# SCH_Record-wav.net
KiCad netlist of a schematic drawn in EasyEDA
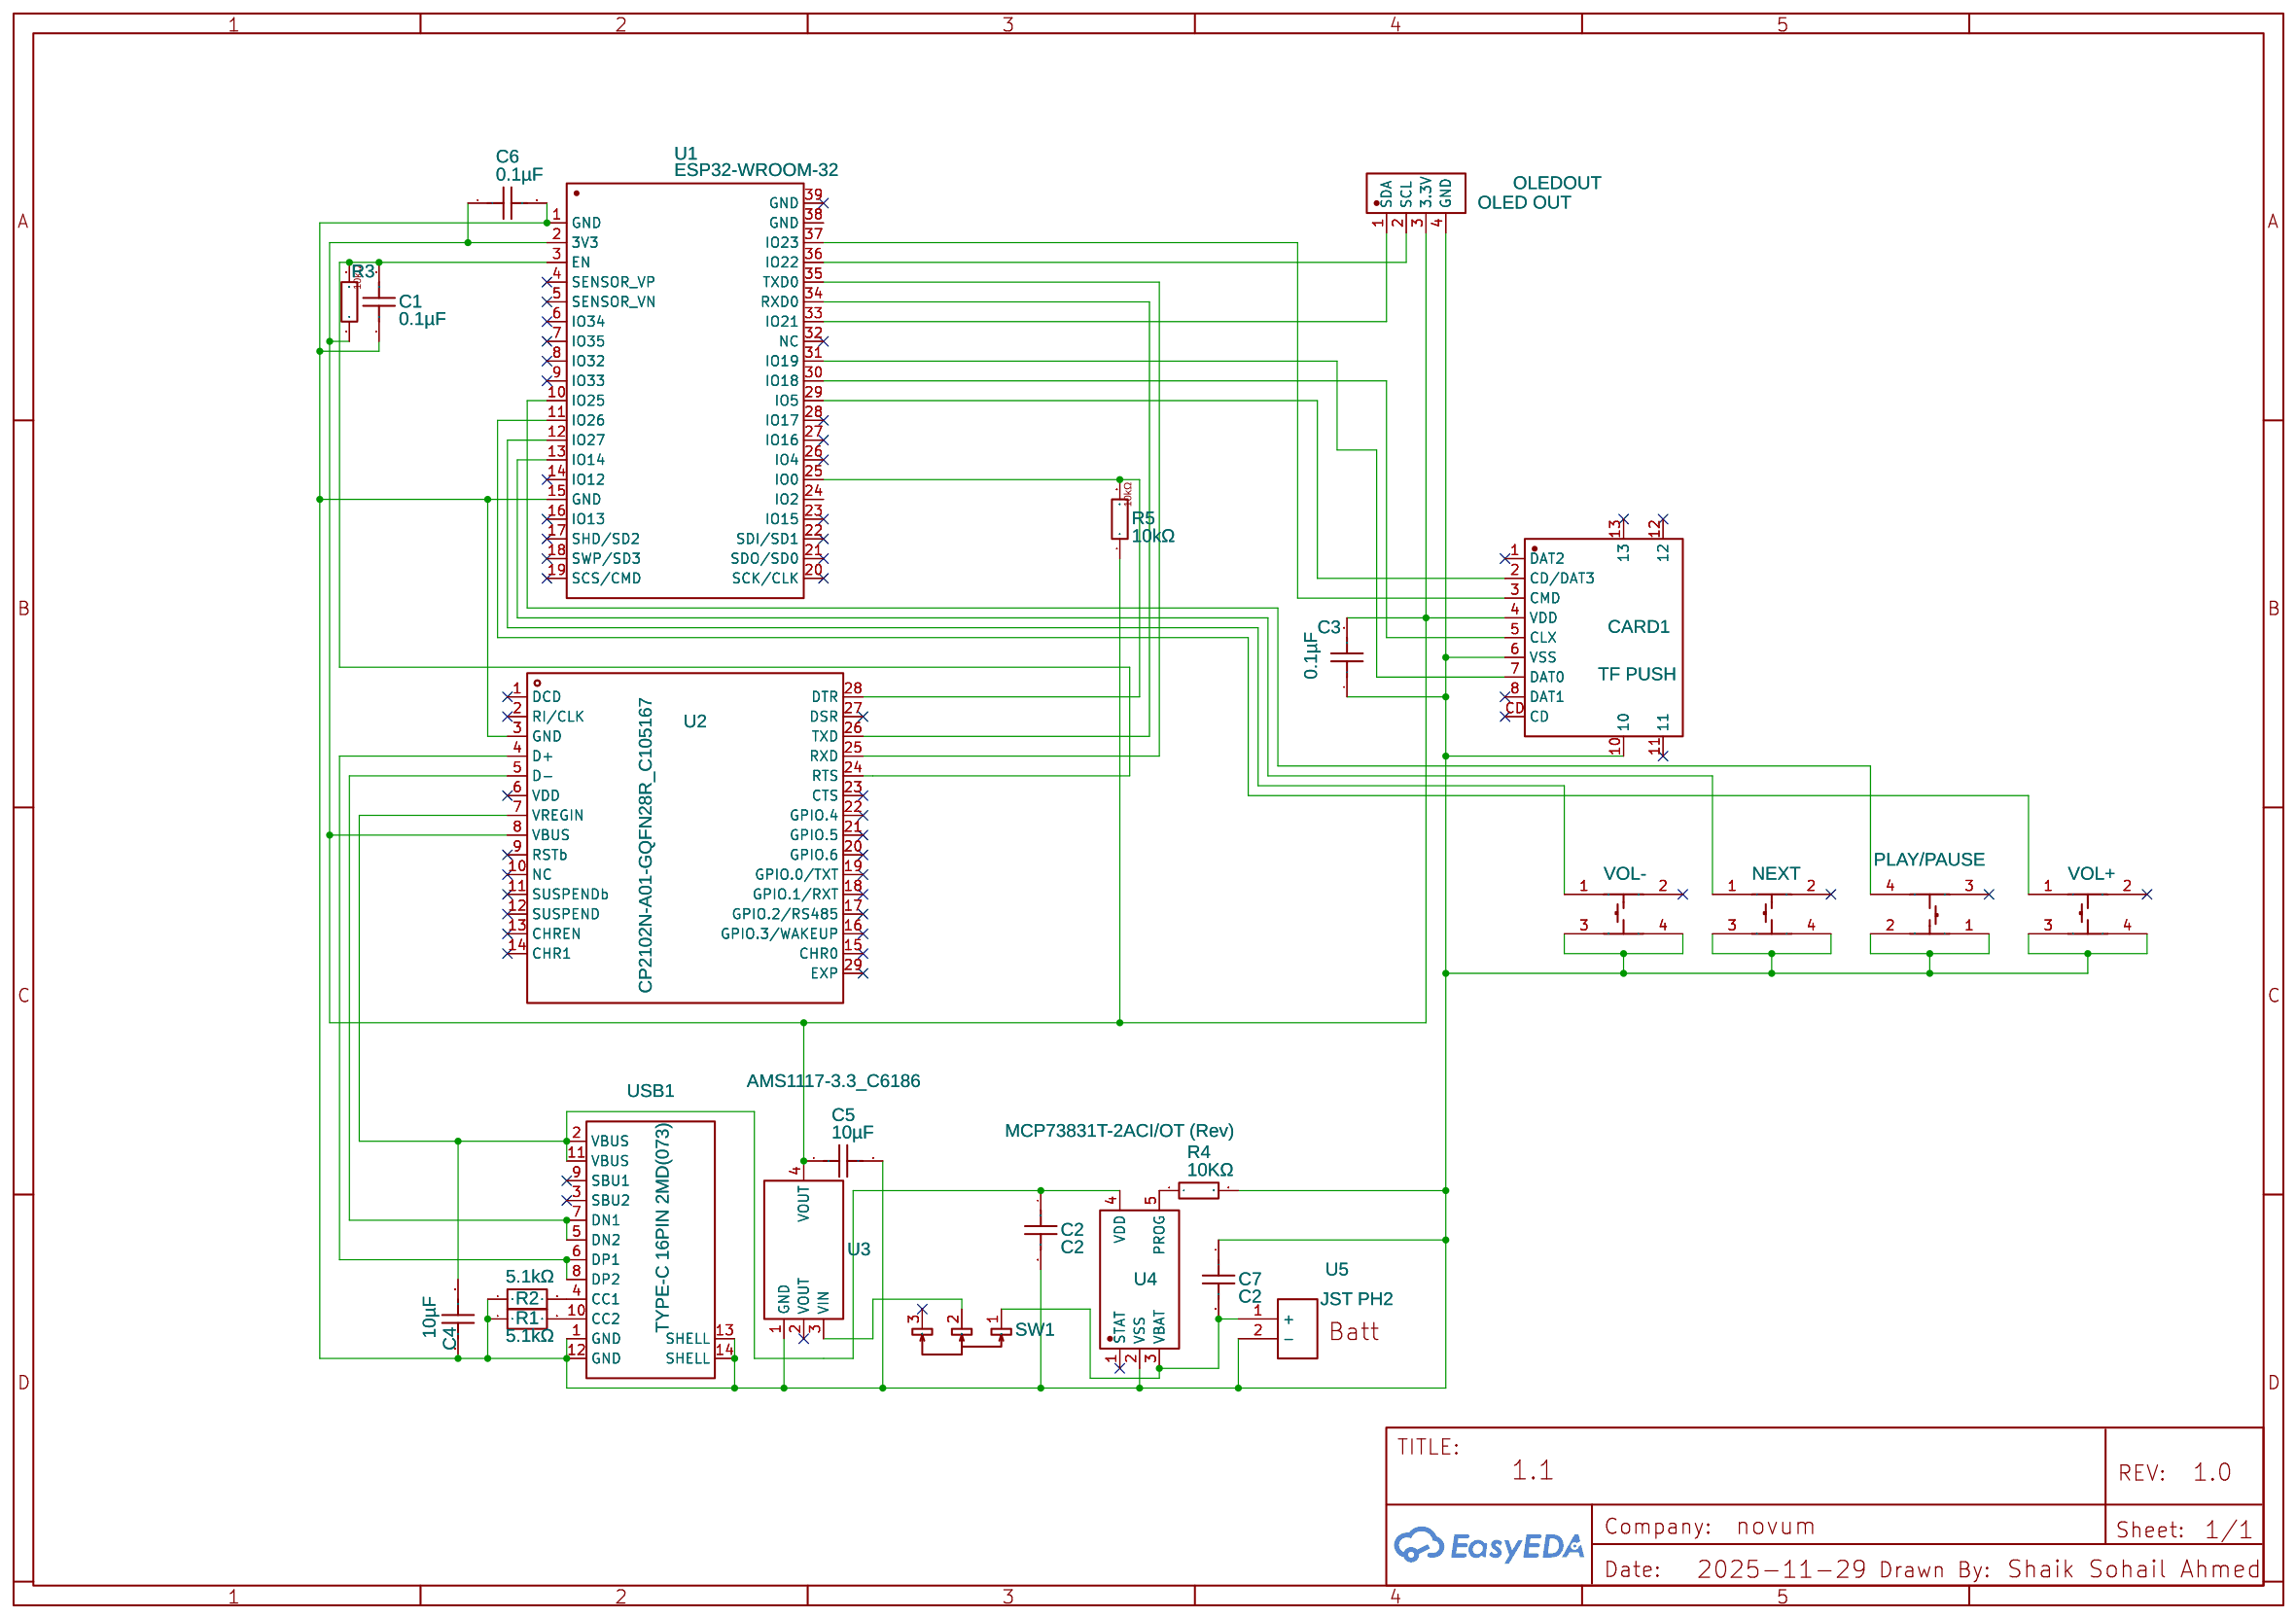
[diagram p0: schematic sheet]

(export (version "E")
  (design (tool "Eeschema 10.0.6"))
  (components
    (comp (ref "C1")
      (value "0.1µF")
      (fields (field (name "Manufacturer Part") "GRM152R60J104ME19D") (field (name "Manufacturer") "muRata"))
      (libsource (lib "") (part "0.1µF_1"))
    )
    (comp (ref "C2")
      (value "C2")
      (fields (field (name "Manufacturer Part") "08053C105JAT2A") (field (name "Manufacturer") "KYOCERA AVX"))
      (libsource (lib "") (part "08053C105JAT2A"))
    )
    (comp (ref "C3")
      (value "0.1µF")
      (fields (field (name "Manufacturer Part") "GRM152R60J104ME19D") (field (name "Manufacturer") "muRata"))
      (libsource (lib "") (part "0.1µF_1"))
    )
    (comp (ref "C4")
      (value "10µF")
      (fields
        (field (name "Manufacturer Part") "CL10A106MA8NRNC")
        (field (name "Manufacturer") "Samsung Electro-Mechanics")
      )
      (libsource (lib "") (part "CL10A106MA8NRNC"))
    )
    (comp (ref "C5")
      (value "10µF")
      (fields
        (field (name "Manufacturer Part") "CL10A106MA8NRNC")
        (field (name "Manufacturer") "Samsung Electro-Mechanics")
      )
      (libsource (lib "") (part "CL10A106MA8NRNC_1"))
    )
    (comp (ref "C6")
      (value "0.1µF")
      (fields (field (name "Manufacturer Part") "GRM152R60J104ME19D") (field (name "Manufacturer") "muRata"))
      (libsource (lib "") (part "0.1µF"))
    )
    (comp (ref "C7")
      (value "C2")
      (fields (field (name "Manufacturer Part") "08053C105JAT2A") (field (name "Manufacturer") "KYOCERA AVX"))
      (libsource (lib "") (part "08053C105JAT2A"))
    )
    (comp (ref "CARD1")
      (value "TF PUSH")
      (fields (field (name "Manufacturer") "SHOU HAN(首韩)"))
      (libsource (lib "") (part "TF PUSH"))
    )
    (comp (ref "NEXT")
      (value "TS-1002S-07026C")
      (fields (field (name "Manufacturer") "XUNPU(讯普)"))
      (libsource (lib "") (part "TS-1002S-07026C_2"))
    )
    (comp (ref "OLEDOUT") (value "OLED OUT") (libsource (lib "") (part "Solder_Pad_4")))
    (comp (ref "PLAY/PAUSE")
      (value "TS-1002S-07026C")
      (fields (field (name "Manufacturer") "XUNPU(讯普)"))
      (libsource (lib "") (part "TS-1002S-07026C_3"))
    )
    (comp (ref "R1")
      (value "5.1kΩ")
      (fields (field (name "Manufacturer Part") "FRC1206F5101TS") (field (name "Manufacturer") "FOJAN(富捷)"))
      (libsource (lib "") (part "5.1KΩ 1/4W ±1% SMD"))
    )
    (comp (ref "R2")
      (value "5.1kΩ")
      (fields (field (name "Manufacturer Part") "FRC1206F5101TS") (field (name "Manufacturer") "FOJAN(富捷)"))
      (libsource (lib "") (part "5.1KΩ 1/4W ±1% SMD"))
    )
    (comp (ref "R3") (value "10kΩ") (libsource (lib "") (part "10kΩ")))
    (comp (ref "R4")
      (value "10KΩ")
      (fields (field (name "Manufacturer Part") "CFR0W4J0103A50") (field (name "Manufacturer") "UniOhm"))
      (libsource (lib "") (part "10KΩ"))
    )
    (comp (ref "R5") (value "10kΩ") (libsource (lib "") (part "10kΩ")))
    (comp (ref "SW1")
      (value "MST-12D18G4 SPDT SLIDE SWITCH")
      (fields
        (field (name "Manufacturer Part") "MST-12D18G4 SPDT Slide Switch")
        (field (name "Manufacturer") "SHOU HAN(首韩)")
      )
      (libsource (lib "") (part "MST-12D18G4 SPDT SLIDE SWITCH"))
    )
    (comp (ref "U1")
      (value "ESP32-WROOM-32")
      (fields
        (field (name "Manufacturer Part") "ESP32-WROOM-32-N4")
        (field (name "Manufacturer") "ESPRESSIF(乐鑫)")
      )
      (libsource (lib "") (part "ESP32-WROOM-32"))
    )
    (comp (ref "U2")
      (value "CP2102N-A01-GQFN28R_C105167")
      (fields
        (field (name "Manufacturer Part") "CP2102N-A01-GQFN28R")
        (field (name "Manufacturer") "SKYWORKS/SILICON LABS(芯科)")
      )
      (libsource (lib "") (part "CP2102N-A01-GQFN28R_C105167"))
    )
    (comp (ref "U3")
      (value "AMS1117-3.3_C6186")
      (fields (field (name "Manufacturer Part") "AMS1117-3.3") (field (name "Manufacturer") "AMS"))
      (libsource (lib "") (part "AMS1117-3.3_C6186"))
    )
    (comp (ref "U4")
      (value "MCP73831T-2ACI/OT (Rev)")
      (fields
        (field (name "Manufacturer Part") "MCP73831T-2ACI/OT")
        (field (name "Manufacturer") "MICROCHIP(美国微芯)")
      )
      (libsource (lib "") (part "MCP73831T-2ACI/OT (Rev)"))
    )
    (comp (ref "U5") (value "JST PH2") (libsource (lib "") (part "JST PH2")))
    (comp (ref "USB1")
      (value "TYPE-C 16PIN 2MD(073)")
      (fields (field (name "Manufacturer") "SHOU HAN(首韩)"))
      (libsource (lib "") (part "TYPE-C 16PIN 2MD(073)"))
    )
    (comp (ref "VOL+")
      (value "TS-1002S-07026C")
      (fields (field (name "Manufacturer") "XUNPU(讯普)"))
      (libsource (lib "") (part "TS-1002S-07026C_1"))
    )
    (comp (ref "VOL-")
      (value "TS-1002S-07026C")
      (fields (field (name "Manufacturer") "XUNPU(讯普)"))
      (libsource (lib "") (part "TS-1002S-07026C"))
    )
  )
  (nets
    (net (code "1") (name "Net-(CARD1-CD{slash}DAT3)") (class "Default")
      (node (ref "CARD1") (pin "2") (pinfunction "CD/DAT3_2") (pintype "unspecified"))
      (node (ref "U1") (pin "29") (pinfunction "IO5_29") (pintype "unspecified"))
    )
    (net (code "2") (name "Net-(CARD1-CLX)") (class "Default")
      (node (ref "CARD1") (pin "5") (pinfunction "CLX_5") (pintype "unspecified"))
      (node (ref "U1") (pin "30") (pinfunction "IO18_30") (pintype "unspecified"))
    )
    (net (code "3") (name "Net-(CARD1-CMD)") (class "Default")
      (node (ref "CARD1") (pin "3") (pinfunction "CMD_3") (pintype "unspecified"))
      (node (ref "U1") (pin "37") (pinfunction "IO23_37") (pintype "unspecified"))
    )
    (net (code "4") (name "Net-(CARD1-DAT0)") (class "Default")
      (node (ref "CARD1") (pin "7") (pinfunction "DAT0_7") (pintype "unspecified"))
      (node (ref "U1") (pin "31") (pinfunction "IO19_31") (pintype "unspecified"))
    )
    (net (code "5") (name "Net-(CARD1-VDD)") (class "Default")
      (node (ref "C3") (pin "2") (pinfunction "2_2") (pintype "unspecified"))
      (node (ref "C5") (pin "1") (pinfunction "1_1") (pintype "unspecified"))
      (node (ref "C6") (pin "1") (pinfunction "1_1") (pintype "unspecified"))
      (node (ref "CARD1") (pin "4") (pinfunction "VDD_4") (pintype "unspecified"))
      (node (ref "OLEDOUT") (pin "3") (pinfunction "3.3V_3") (pintype "unspecified"))
      (node (ref "R3") (pin "1") (pinfunction "1_1") (pintype "unspecified"))
      (node (ref "R5") (pin "1") (pinfunction "1_1") (pintype "unspecified"))
      (node (ref "U1") (pin "2") (pinfunction "3V3_2") (pintype "unspecified"))
      (node (ref "U2") (pin "8") (pinfunction "VBUS_8") (pintype "unspecified"))
      (node (ref "U3") (pin "4") (pinfunction "VOUT_4") (pintype "unspecified"))
    )
    (net (code "6") (name "Net-(CARD1-VSS)") (class "Default")
      (node (ref "C1") (pin "1") (pinfunction "1_1") (pintype "unspecified"))
      (node (ref "C2") (pin "2") (pinfunction "2_2") (pintype "unspecified"))
      (node (ref "C3") (pin "1") (pinfunction "1_1") (pintype "unspecified"))
      (node (ref "C4") (pin "2") (pinfunction "2_2") (pintype "unspecified"))
      (node (ref "C5") (pin "2") (pinfunction "2_2") (pintype "unspecified"))
      (node (ref "C6") (pin "2") (pinfunction "2_2") (pintype "unspecified"))
      (node (ref "C7") (pin "1") (pinfunction "1_1") (pintype "unspecified"))
      (node (ref "CARD1") (pin "10") (pinfunction "10_10") (pintype "unspecified"))
      (node (ref "CARD1") (pin "6") (pinfunction "VSS_6") (pintype "unspecified"))
      (node (ref "NEXT") (pin "3") (pinfunction "3_3") (pintype "unspecified"))
      (node (ref "NEXT") (pin "4") (pinfunction "4_4") (pintype "unspecified"))
      (node (ref "OLEDOUT") (pin "4") (pinfunction "GND_4") (pintype "unspecified"))
      (node (ref "PLAY/PAUSE") (pin "1") (pinfunction "1_1") (pintype "unspecified"))
      (node (ref "PLAY/PAUSE") (pin "2") (pinfunction "2_2") (pintype "unspecified"))
      (node (ref "R1") (pin "1") (pinfunction "1_1") (pintype "unspecified"))
      (node (ref "R2") (pin "1") (pinfunction "1_1") (pintype "unspecified"))
      (node (ref "R4") (pin "2") (pinfunction "2_2") (pintype "input"))
      (node (ref "U1") (pin "1") (pinfunction "GND_1") (pintype "unspecified"))
      (node (ref "U1") (pin "15") (pinfunction "GND_15") (pintype "unspecified"))
      (node (ref "U2") (pin "3") (pinfunction "GND_3") (pintype "unspecified"))
      (node (ref "U3") (pin "1") (pinfunction "GND_1") (pintype "unspecified"))
      (node (ref "U4") (pin "2") (pinfunction "VSS_2") (pintype "unspecified"))
      (node (ref "U5") (pin "2") (pinfunction "-_2") (pintype "unspecified"))
      (node (ref "USB1") (pin "1") (pinfunction "GND_1") (pintype "unspecified"))
      (node (ref "USB1") (pin "12") (pinfunction "GND_12") (pintype "unspecified"))
      (node (ref "USB1") (pin "13") (pinfunction "SHELL_13") (pintype "unspecified"))
      (node (ref "USB1") (pin "14") (pinfunction "SHELL_14") (pintype "unspecified"))
      (node (ref "VOL+") (pin "3") (pinfunction "3_3") (pintype "unspecified"))
      (node (ref "VOL+") (pin "4") (pinfunction "4_4") (pintype "unspecified"))
      (node (ref "VOL-") (pin "3") (pinfunction "3_3") (pintype "unspecified"))
      (node (ref "VOL-") (pin "4") (pinfunction "4_4") (pintype "unspecified"))
    )
    (net (code "7") (name "Net-(OLEDOUT-SCL)") (class "Default")
      (node (ref "OLEDOUT") (pin "2") (pinfunction "SCL_2") (pintype "unspecified"))
      (node (ref "U1") (pin "36") (pinfunction "IO22_36") (pintype "unspecified"))
    )
    (net (code "8") (name "Net-(OLEDOUT-SDA)") (class "Default")
      (node (ref "OLEDOUT") (pin "1") (pinfunction "SDA_1") (pintype "unspecified"))
      (node (ref "U1") (pin "33") (pinfunction "IO21_33") (pintype "unspecified"))
    )
    (net (code "9") (name "Net-(U1-EN)") (class "Default")
      (node (ref "C1") (pin "2") (pinfunction "2_2") (pintype "unspecified"))
      (node (ref "R3") (pin "2") (pinfunction "2_2") (pintype "unspecified"))
      (node (ref "U1") (pin "3") (pinfunction "EN_3") (pintype "unspecified"))
      (node (ref "U2") (pin "24") (pinfunction "RTS_24") (pintype "unspecified"))
    )
    (net (code "10") (name "Net-(U1-IO0)") (class "Default")
      (node (ref "R5") (pin "2") (pinfunction "2_2") (pintype "unspecified"))
      (node (ref "U1") (pin "25") (pinfunction "IO0_25") (pintype "unspecified"))
      (node (ref "U2") (pin "28") (pinfunction "DTR_28") (pintype "unspecified"))
    )
    (net (code "11") (name "Net-(U1-IO14)") (class "Default")
      (node (ref "NEXT") (pin "1") (pinfunction "1_1") (pintype "unspecified"))
      (node (ref "U1") (pin "13") (pinfunction "IO14_13") (pintype "unspecified"))
    )
    (net (code "12") (name "Net-(U1-IO25)") (class "Default")
      (node (ref "PLAY/PAUSE") (pin "4") (pinfunction "4_4") (pintype "unspecified"))
      (node (ref "U1") (pin "10") (pinfunction "IO25_10") (pintype "unspecified"))
    )
    (net (code "13") (name "Net-(U1-IO26)") (class "Default")
      (node (ref "U1") (pin "11") (pinfunction "IO26_11") (pintype "unspecified"))
      (node (ref "VOL+") (pin "1") (pinfunction "1_1") (pintype "unspecified"))
    )
    (net (code "14") (name "Net-(U1-IO27)") (class "Default")
      (node (ref "U1") (pin "12") (pinfunction "IO27_12") (pintype "unspecified"))
      (node (ref "VOL-") (pin "1") (pinfunction "1_1") (pintype "unspecified"))
    )
    (net (code "15") (name "Net-(U1-RXD0)") (class "Default")
      (node (ref "U1") (pin "34") (pinfunction "RXD0_34") (pintype "unspecified"))
      (node (ref "U2") (pin "26") (pinfunction "TXD_26") (pintype "unspecified"))
    )
    (net (code "16") (name "Net-(U1-TXD0)") (class "Default")
      (node (ref "U1") (pin "35") (pinfunction "TXD0_35") (pintype "unspecified"))
      (node (ref "U2") (pin "25") (pinfunction "RXD_25") (pintype "unspecified"))
    )
    (net (code "17") (name "Net-(U2-D+)") (class "Default")
      (node (ref "U2") (pin "4") (pinfunction "D+_4") (pintype "unspecified"))
      (node (ref "USB1") (pin "6") (pinfunction "DP1_6") (pintype "unspecified"))
      (node (ref "USB1") (pin "8") (pinfunction "DP2_8") (pintype "unspecified"))
    )
    (net (code "18") (name "Net-(U2-D-)") (class "Default")
      (node (ref "U2") (pin "5") (pinfunction "D-_5") (pintype "unspecified"))
      (node (ref "USB1") (pin "5") (pinfunction "DN2_5") (pintype "unspecified"))
      (node (ref "USB1") (pin "7") (pinfunction "DN1_7") (pintype "unspecified"))
    )
    (net (code "19") (name "Net-(U2-VREGIN)") (class "Default")
      (node (ref "C2") (pin "1") (pinfunction "1_1") (pintype "unspecified"))
      (node (ref "C4") (pin "1") (pinfunction "1_1") (pintype "unspecified"))
      (node (ref "U2") (pin "7") (pinfunction "VREGIN_7") (pintype "unspecified"))
      (node (ref "U4") (pin "4") (pinfunction "VDD_4") (pintype "unspecified"))
      (node (ref "USB1") (pin "11") (pinfunction "VBUS_11") (pintype "unspecified"))
      (node (ref "USB1") (pin "2") (pinfunction "VBUS_2") (pintype "unspecified"))
    )
    (net (code "20") (name "Net-(U3-VIN)") (class "Default")
      (node (ref "SW1") (pin "2") (pinfunction "2_2") (pintype "unspecified"))
      (node (ref "U3") (pin "3") (pinfunction "VIN_3") (pintype "unspecified"))
    )
    (net (code "21") (name "Net-(U4-PROG)") (class "Default")
      (node (ref "R4") (pin "1") (pinfunction "1_1") (pintype "input"))
      (node (ref "U4") (pin "5") (pinfunction "PROG_5") (pintype "unspecified"))
    )
    (net (code "22") (name "Net-(U4-VBAT)") (class "Default")
      (node (ref "C7") (pin "2") (pinfunction "2_2") (pintype "unspecified"))
      (node (ref "SW1") (pin "1") (pinfunction "1_1") (pintype "unspecified"))
      (node (ref "U4") (pin "3") (pinfunction "VBAT_3") (pintype "unspecified"))
      (node (ref "U5") (pin "1") (pinfunction "+_1") (pintype "unspecified"))
    )
    (net (code "23") (name "Net-(USB1-CC1)") (class "Default")
      (node (ref "R2") (pin "2") (pinfunction "2_2") (pintype "unspecified"))
      (node (ref "USB1") (pin "4") (pinfunction "CC1_4") (pintype "unspecified"))
    )
    (net (code "24") (name "Net-(USB1-CC2)") (class "Default")
      (node (ref "R1") (pin "2") (pinfunction "2_2") (pintype "unspecified"))
      (node (ref "USB1") (pin "10") (pinfunction "CC2_10") (pintype "unspecified"))
    )
    (net (code "25") (name "unconnected-(CARD1-DAT1-Pad8)") (class "Default")
      (node (ref "CARD1") (pin "8") (pinfunction "DAT1_8") (pintype "unspecified+no_connect"))
    )
    (net (code "26") (name "unconnected-(CARD1-DAT2-Pad1)") (class "Default")
      (node (ref "CARD1") (pin "1") (pinfunction "DAT2_1") (pintype "unspecified+no_connect"))
    )
    (net (code "27") (name "unconnected-(CARD1-Pad11)") (class "Default")
      (node (ref "CARD1") (pin "11") (pinfunction "11_11") (pintype "unspecified+no_connect"))
    )
    (net (code "28") (name "unconnected-(CARD1-Pad12)") (class "Default")
      (node (ref "CARD1") (pin "12") (pinfunction "12_12") (pintype "unspecified+no_connect"))
    )
    (net (code "29") (name "unconnected-(CARD1-Pad13)") (class "Default")
      (node (ref "CARD1") (pin "13") (pinfunction "13_13") (pintype "unspecified+no_connect"))
    )
    (net (code "30") (name "unconnected-(CARD1-PadCD)") (class "Default")
      (node (ref "CARD1") (pin "CD") (pinfunction "CD_CD") (pintype "unspecified+no_connect"))
    )
    (net (code "31") (name "unconnected-(NEXT-Pad2)") (class "Default")
      (node (ref "NEXT") (pin "2") (pinfunction "2_2") (pintype "unspecified+no_connect"))
    )
    (net (code "32") (name "unconnected-(PLAY/PAUSE-Pad3)") (class "Default")
      (node (ref "PLAY/PAUSE") (pin "3") (pinfunction "3_3") (pintype "unspecified+no_connect"))
    )
    (net (code "33") (name "unconnected-(SW1-Pad3)") (class "Default")
      (node (ref "SW1") (pin "3") (pinfunction "3_3") (pintype "unspecified+no_connect"))
    )
    (net (code "34") (name "unconnected-(U1-GND-Pad38)") (class "Default")
      (node (ref "U1") (pin "38") (pinfunction "GND_38") (pintype "unspecified"))
    )
    (net (code "35") (name "unconnected-(U1-GND-Pad39)") (class "Default")
      (node (ref "U1") (pin "39") (pinfunction "GND_39") (pintype "unspecified+no_connect"))
    )
    (net (code "36") (name "unconnected-(U1-IO2-Pad24)") (class "Default")
      (node (ref "U1") (pin "24") (pinfunction "IO2_24") (pintype "unspecified"))
    )
    (net (code "37") (name "unconnected-(U1-IO4-Pad26)") (class "Default")
      (node (ref "U1") (pin "26") (pinfunction "IO4_26") (pintype "unspecified+no_connect"))
    )
    (net (code "38") (name "unconnected-(U1-IO12-Pad14)") (class "Default")
      (node (ref "U1") (pin "14") (pinfunction "IO12_14") (pintype "unspecified+no_connect"))
    )
    (net (code "39") (name "unconnected-(U1-IO13-Pad16)") (class "Default")
      (node (ref "U1") (pin "16") (pinfunction "IO13_16") (pintype "unspecified+no_connect"))
    )
    (net (code "40") (name "unconnected-(U1-IO15-Pad23)") (class "Default")
      (node (ref "U1") (pin "23") (pinfunction "IO15_23") (pintype "unspecified+no_connect"))
    )
    (net (code "41") (name "unconnected-(U1-IO16-Pad27)") (class "Default")
      (node (ref "U1") (pin "27") (pinfunction "IO16_27") (pintype "unspecified+no_connect"))
    )
    (net (code "42") (name "unconnected-(U1-IO17-Pad28)") (class "Default")
      (node (ref "U1") (pin "28") (pinfunction "IO17_28") (pintype "unspecified+no_connect"))
    )
    (net (code "43") (name "unconnected-(U1-IO32-Pad8)") (class "Default")
      (node (ref "U1") (pin "8") (pinfunction "IO32_8") (pintype "unspecified+no_connect"))
    )
    (net (code "44") (name "unconnected-(U1-IO33-Pad9)") (class "Default")
      (node (ref "U1") (pin "9") (pinfunction "IO33_9") (pintype "unspecified+no_connect"))
    )
    (net (code "45") (name "unconnected-(U1-IO34-Pad6)") (class "Default")
      (node (ref "U1") (pin "6") (pinfunction "IO34_6") (pintype "unspecified+no_connect"))
    )
    (net (code "46") (name "unconnected-(U1-IO35-Pad7)") (class "Default")
      (node (ref "U1") (pin "7") (pinfunction "IO35_7") (pintype "unspecified+no_connect"))
    )
    (net (code "47") (name "unconnected-(U1-NC-Pad32)") (class "Default")
      (node (ref "U1") (pin "32") (pinfunction "NC_32") (pintype "unspecified+no_connect"))
    )
    (net (code "48") (name "unconnected-(U1-SCK{slash}CLK-Pad20)") (class "Default")
      (node (ref "U1") (pin "20") (pinfunction "SCK/CLK_20") (pintype "unspecified+no_connect"))
    )
    (net (code "49") (name "unconnected-(U1-SCS{slash}CMD-Pad19)") (class "Default")
      (node (ref "U1") (pin "19") (pinfunction "SCS/CMD_19") (pintype "unspecified+no_connect"))
    )
    (net (code "50") (name "unconnected-(U1-SDI{slash}SD1-Pad22)") (class "Default")
      (node (ref "U1") (pin "22") (pinfunction "SDI/SD1_22") (pintype "unspecified+no_connect"))
    )
    (net (code "51") (name "unconnected-(U1-SDO{slash}SD0-Pad21)") (class "Default")
      (node (ref "U1") (pin "21") (pinfunction "SDO/SD0_21") (pintype "unspecified+no_connect"))
    )
    (net (code "52") (name "unconnected-(U1-SENSOR_VN-Pad5)") (class "Default")
      (node (ref "U1") (pin "5") (pinfunction "SENSOR_VN_5") (pintype "unspecified+no_connect"))
    )
    (net (code "53") (name "unconnected-(U1-SENSOR_VP-Pad4)") (class "Default")
      (node (ref "U1") (pin "4") (pinfunction "SENSOR_VP_4") (pintype "unspecified+no_connect"))
    )
    (net (code "54") (name "unconnected-(U1-SHD{slash}SD2-Pad17)") (class "Default")
      (node (ref "U1") (pin "17") (pinfunction "SHD/SD2_17") (pintype "unspecified+no_connect"))
    )
    (net (code "55") (name "unconnected-(U1-SWP{slash}SD3-Pad18)") (class "Default")
      (node (ref "U1") (pin "18") (pinfunction "SWP/SD3_18") (pintype "unspecified+no_connect"))
    )
    (net (code "56") (name "unconnected-(U2-CHR0-Pad15)") (class "Default")
      (node (ref "U2") (pin "15") (pinfunction "CHR0_15") (pintype "unspecified+no_connect"))
    )
    (net (code "57") (name "unconnected-(U2-CHR1-Pad14)") (class "Default")
      (node (ref "U2") (pin "14") (pinfunction "CHR1_14") (pintype "unspecified+no_connect"))
    )
    (net (code "58") (name "unconnected-(U2-CHREN-Pad13)") (class "Default")
      (node (ref "U2") (pin "13") (pinfunction "CHREN_13") (pintype "unspecified+no_connect"))
    )
    (net (code "59") (name "unconnected-(U2-CTS-Pad23)") (class "Default")
      (node (ref "U2") (pin "23") (pinfunction "CTS_23") (pintype "unspecified+no_connect"))
    )
    (net (code "60") (name "unconnected-(U2-DCD-Pad1)") (class "Default")
      (node (ref "U2") (pin "1") (pinfunction "DCD_1") (pintype "unspecified+no_connect"))
    )
    (net (code "61") (name "unconnected-(U2-DSR-Pad27)") (class "Default")
      (node (ref "U2") (pin "27") (pinfunction "DSR_27") (pintype "unspecified+no_connect"))
    )
    (net (code "62") (name "unconnected-(U2-EXP-Pad29)") (class "Default")
      (node (ref "U2") (pin "29") (pinfunction "EXP_29") (pintype "unspecified+no_connect"))
    )
    (net (code "63") (name "unconnected-(U2-GPIO.0{slash}TXT-Pad19)") (class "Default")
      (node (ref "U2") (pin "19") (pinfunction "GPIO.0/TXT_19") (pintype "unspecified+no_connect"))
    )
    (net (code "64") (name "unconnected-(U2-GPIO.1{slash}RXT-Pad18)") (class "Default")
      (node (ref "U2") (pin "18") (pinfunction "GPIO.1/RXT_18") (pintype "unspecified+no_connect"))
    )
    (net (code "65") (name "unconnected-(U2-GPIO.2{slash}RS485-Pad17)") (class "Default")
      (node (ref "U2") (pin "17") (pinfunction "GPIO.2/RS485_17") (pintype "unspecified+no_connect"))
    )
    (net (code "66") (name "unconnected-(U2-GPIO.3{slash}WAKEUP-Pad16)") (class "Default")
      (node (ref "U2") (pin "16") (pinfunction "GPIO.3/WAKEUP_16") (pintype "unspecified+no_connect"))
    )
    (net (code "67") (name "unconnected-(U2-GPIO.4-Pad22)") (class "Default")
      (node (ref "U2") (pin "22") (pinfunction "GPIO.4_22") (pintype "unspecified+no_connect"))
    )
    (net (code "68") (name "unconnected-(U2-GPIO.5-Pad21)") (class "Default")
      (node (ref "U2") (pin "21") (pinfunction "GPIO.5_21") (pintype "unspecified+no_connect"))
    )
    (net (code "69") (name "unconnected-(U2-GPIO.6-Pad20)") (class "Default")
      (node (ref "U2") (pin "20") (pinfunction "GPIO.6_20") (pintype "unspecified+no_connect"))
    )
    (net (code "70") (name "unconnected-(U2-NC-Pad10)") (class "Default")
      (node (ref "U2") (pin "10") (pinfunction "NC_10") (pintype "unspecified+no_connect"))
    )
    (net (code "71") (name "unconnected-(U2-RI{slash}CLK-Pad2)") (class "Default")
      (node (ref "U2") (pin "2") (pinfunction "RI/CLK_2") (pintype "unspecified+no_connect"))
    )
    (net (code "72") (name "unconnected-(U2-RSTb-Pad9)") (class "Default")
      (node (ref "U2") (pin "9") (pinfunction "RSTb_9") (pintype "unspecified+no_connect"))
    )
    (net (code "73") (name "unconnected-(U2-SUSPEND-Pad12)") (class "Default")
      (node (ref "U2") (pin "12") (pinfunction "SUSPEND_12") (pintype "unspecified+no_connect"))
    )
    (net (code "74") (name "unconnected-(U2-SUSPENDb-Pad11)") (class "Default")
      (node (ref "U2") (pin "11") (pinfunction "SUSPENDb_11") (pintype "unspecified+no_connect"))
    )
    (net (code "75") (name "unconnected-(U2-VDD-Pad6)") (class "Default")
      (node (ref "U2") (pin "6") (pinfunction "VDD_6") (pintype "unspecified+no_connect"))
    )
    (net (code "76") (name "unconnected-(U3-VOUT-Pad2)") (class "Default")
      (node (ref "U3") (pin "2") (pinfunction "VOUT_2") (pintype "unspecified+no_connect"))
    )
    (net (code "77") (name "unconnected-(U4-STAT-Pad1)") (class "Default")
      (node (ref "U4") (pin "1") (pinfunction "STAT_1") (pintype "unspecified+no_connect"))
    )
    (net (code "78") (name "unconnected-(USB1-SBU1-Pad9)") (class "Default")
      (node (ref "USB1") (pin "9") (pinfunction "SBU1_9") (pintype "unspecified+no_connect"))
    )
    (net (code "79") (name "unconnected-(USB1-SBU2-Pad3)") (class "Default")
      (node (ref "USB1") (pin "3") (pinfunction "SBU2_3") (pintype "unspecified+no_connect"))
    )
    (net (code "80") (name "unconnected-(VOL+-Pad2)") (class "Default")
      (node (ref "VOL+") (pin "2") (pinfunction "2_2") (pintype "unspecified+no_connect"))
    )
    (net (code "81") (name "unconnected-(VOL--Pad2)") (class "Default")
      (node (ref "VOL-") (pin "2") (pinfunction "2_2") (pintype "unspecified+no_connect"))
    )
  )
)
